# dual-motor-driver.net
KiCad netlist of a schematic drawn in Altium Designer
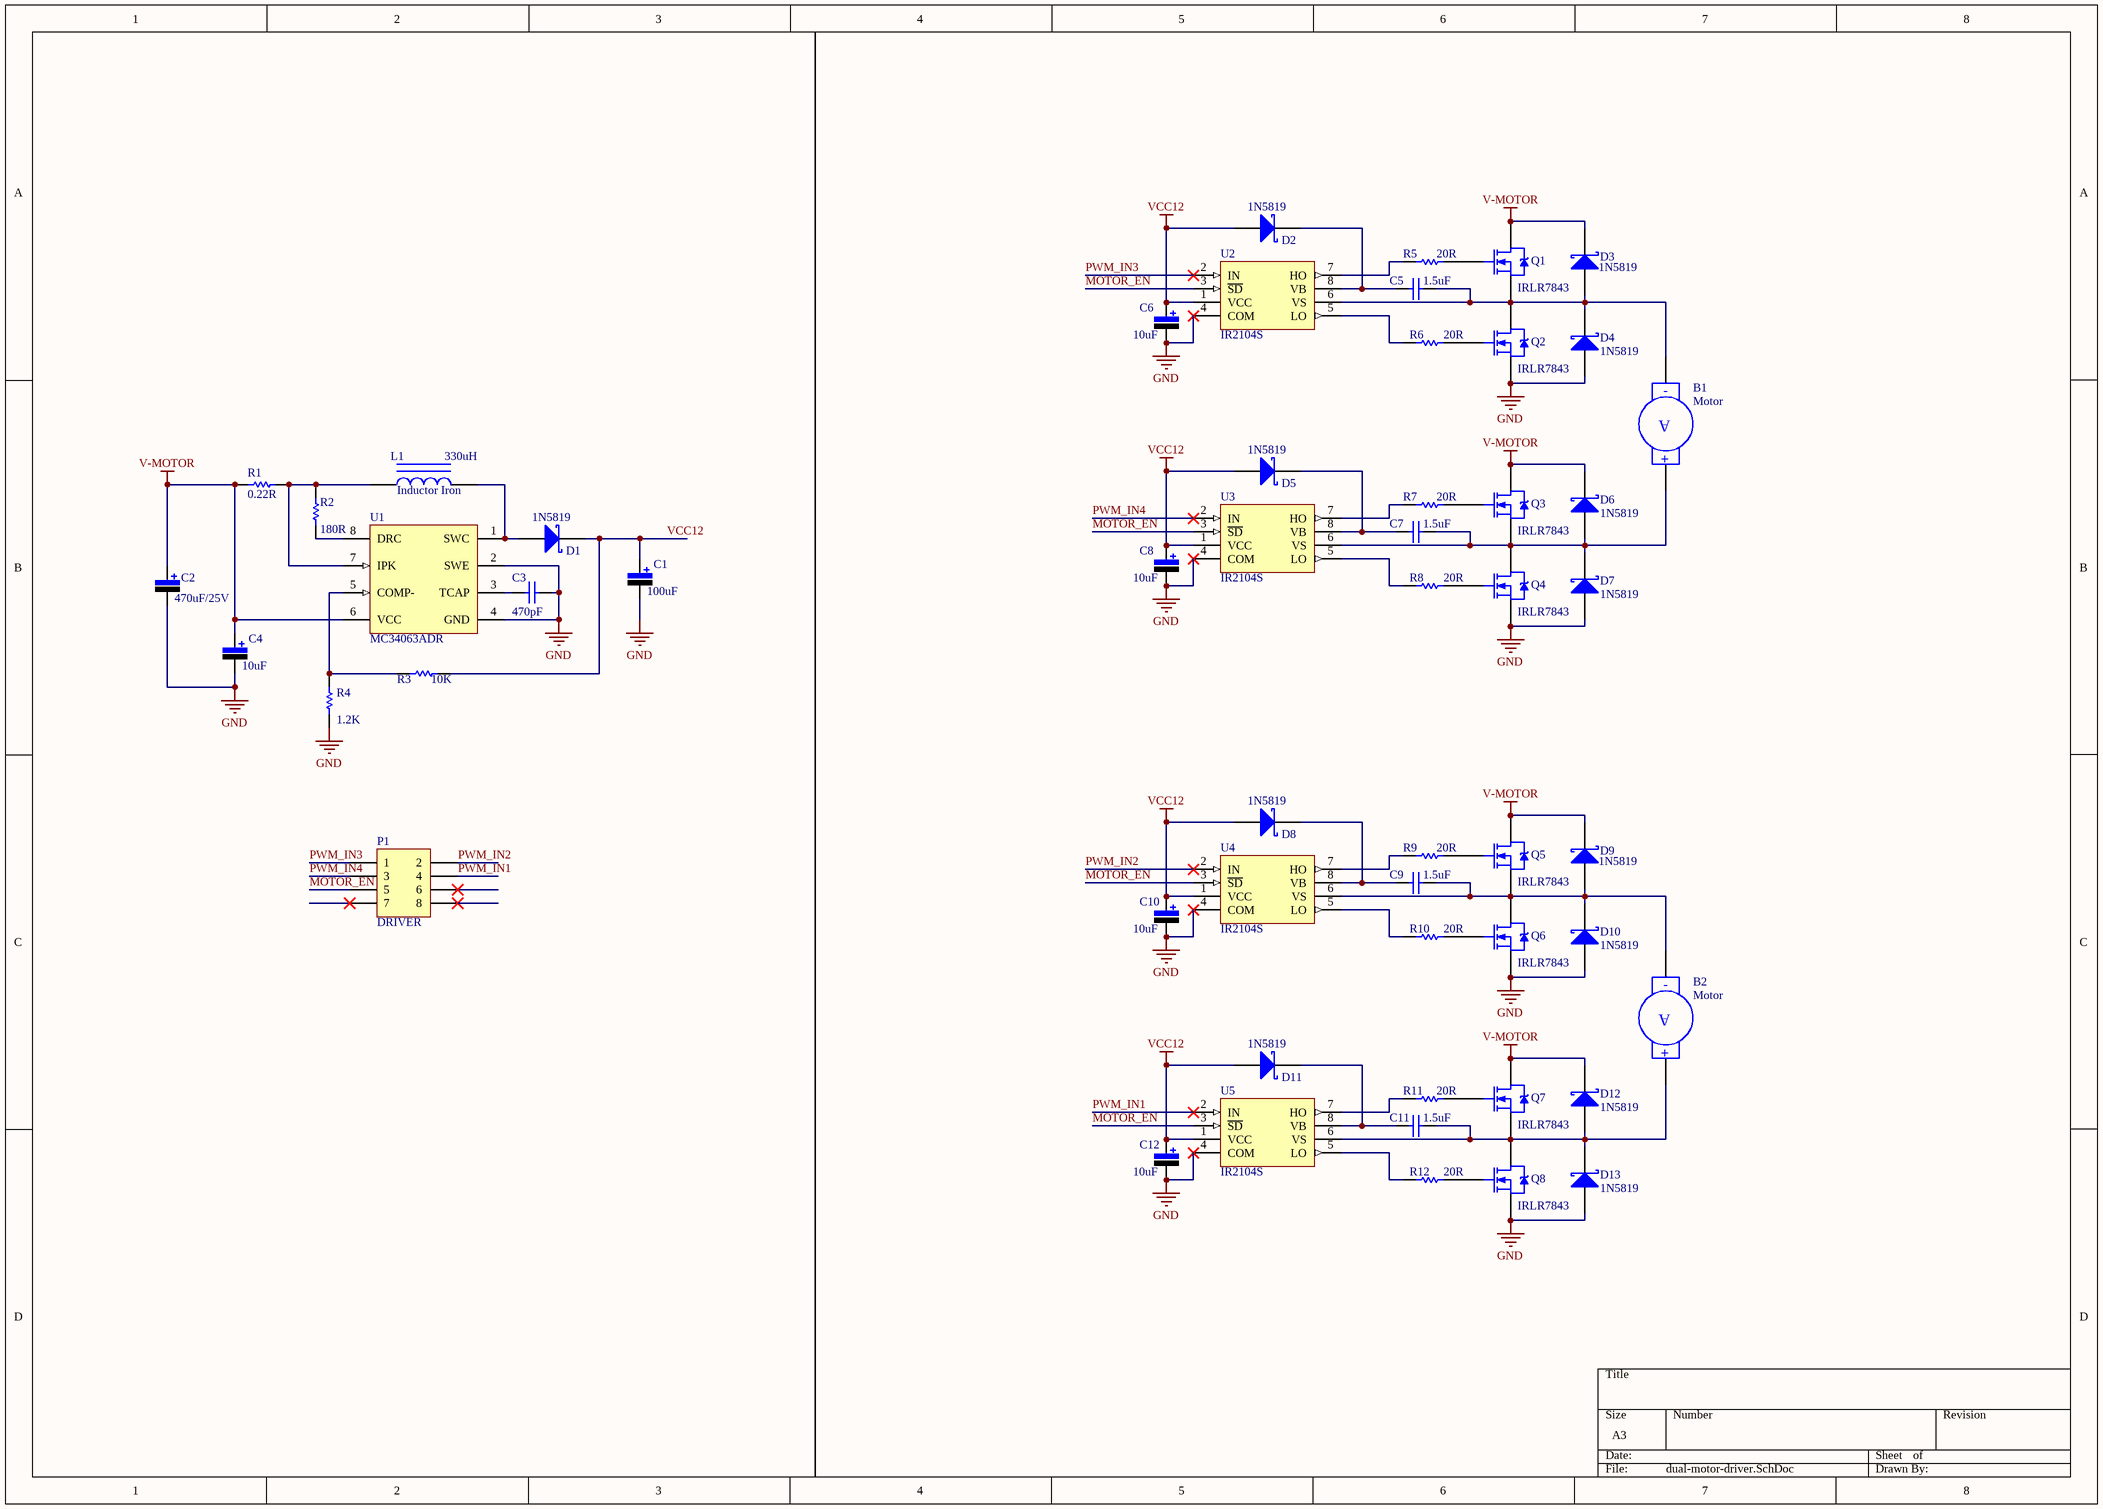
[diagram p0: dual-motor-driver.SchDoc]

(export (version "E")
  (design (tool "Eeschema 10.0.6"))
  (components
    (comp (ref "B1")
      (value "Motor")
      (footprint "Con 2接线端子")
      (description "Servo Motor")
      (fields (field (name "PUBLISHER") "Altium Limited"))
      (libsource (lib "Miscellaneous Devices") (part "Motor Servo"))
    )
    (comp (ref "B2")
      (value "Motor")
      (footprint "Con 2接线端子")
      (description "Servo Motor")
      (fields (field (name "PUBLISHER") "Altium Limited"))
      (libsource (lib "Miscellaneous Devices") (part "Motor Servo"))
    )
    (comp (ref "C1")
      (value "100uF")
      (footprint "LC-CASE-D_7343")
      (description "钽电容")
      (fields (field (name "Comment") "Cap-Pol") (field (name "PUBLISHER") "Altium Limited"))
      (libsource (lib "Fszhang") (part "Cap-Pol-A"))
    )
    (comp (ref "C2")
      (value "470uF/25V")
      (footprint "C-RB-3.5/8")
      (description "贴片铝电解电容")
      (fields (field (name "Comment") "Cap-Pol-ES") (field (name "PUBLISHER") "Altium Limited"))
      (libsource (lib "Fszhang") (part "Cap-Pol-ES"))
    )
    (comp (ref "C3")
      (value "470pF")
      (footprint "LC-0603_C")
      (description "Capacitor")
      (fields (field (name "Comment") "Cap") (field (name "PUBLISHER") "Altium Limited"))
      (libsource (lib "Miscellaneous Devices") (part "Cap"))
    )
    (comp (ref "C4")
      (value "10uF")
      (footprint "LC-CASE-C_6032")
      (description "钽电容")
      (fields (field (name "Comment") "Cap-Pol") (field (name "PUBLISHER") "Altium Limited"))
      (libsource (lib "Fszhang") (part "Cap-Pol-A"))
    )
    (comp (ref "C5")
      (value "1.5uF")
      (footprint "LC-0805_C")
      (description "Capacitor")
      (fields (field (name "Comment") "Cap") (field (name "PUBLISHER") "Altium Limited"))
      (libsource (lib "Miscellaneous Devices") (part "Cap"))
    )
    (comp (ref "C6")
      (value "10uF")
      (footprint "LC-CASE-C_6032")
      (description "钽电容")
      (fields (field (name "Comment") "Cap-Pol") (field (name "PUBLISHER") "Altium Limited"))
      (libsource (lib "Fszhang") (part "Cap-Pol-A"))
    )
    (comp (ref "C7")
      (value "1.5uF")
      (footprint "LC-0805_C")
      (description "Capacitor")
      (fields (field (name "Comment") "Cap") (field (name "PUBLISHER") "Altium Limited"))
      (libsource (lib "Miscellaneous Devices") (part "Cap"))
    )
    (comp (ref "C8")
      (value "10uF")
      (footprint "LC-CASE-C_6032")
      (description "钽电容")
      (fields (field (name "Comment") "Cap-Pol") (field (name "PUBLISHER") "Altium Limited"))
      (libsource (lib "Fszhang") (part "Cap-Pol-A"))
    )
    (comp (ref "C9")
      (value "1.5uF")
      (footprint "LC-0805_C")
      (description "Capacitor")
      (fields (field (name "Comment") "Cap") (field (name "PUBLISHER") "Altium Limited"))
      (libsource (lib "Miscellaneous Devices") (part "Cap"))
    )
    (comp (ref "C10")
      (value "10uF")
      (footprint "LC-CASE-C_6032")
      (description "钽电容")
      (fields (field (name "Comment") "Cap-Pol") (field (name "PUBLISHER") "Altium Limited"))
      (libsource (lib "Fszhang") (part "Cap-Pol-A"))
    )
    (comp (ref "C11")
      (value "1.5uF")
      (footprint "LC-0805_C")
      (description "Capacitor")
      (fields (field (name "Comment") "Cap") (field (name "PUBLISHER") "Altium Limited"))
      (libsource (lib "Miscellaneous Devices") (part "Cap"))
    )
    (comp (ref "C12")
      (value "10uF")
      (footprint "LC-CASE-C_6032")
      (description "钽电容")
      (fields (field (name "Comment") "Cap-Pol") (field (name "PUBLISHER") "Altium Limited"))
      (libsource (lib "Fszhang") (part "Cap-Pol-A"))
    )
    (comp (ref "D1")
      (value "1N5819")
      (footprint "LC-SMA(DO-214AC)_S1")
      (description "Schottky Diode")
      (fields (field (name "PUBLISHER") "Altium Limited"))
      (libsource (lib "Miscellaneous Devices") (part "D Schottky"))
    )
    (comp (ref "D2")
      (value "1N5819")
      (footprint "LC-SMA(DO-214AC)_S1")
      (description "Schottky Diode")
      (fields (field (name "PUBLISHER") "Altium Limited"))
      (libsource (lib "Miscellaneous Devices") (part "D Schottky"))
    )
    (comp (ref "D3")
      (value "1N5819")
      (footprint "LC-SMA(DO-214AC)_S1")
      (description "Schottky Diode")
      (fields (field (name "PUBLISHER") "Altium Limited"))
      (libsource (lib "Miscellaneous Devices") (part "D Schottky"))
    )
    (comp (ref "D4")
      (value "1N5819")
      (footprint "LC-SMA(DO-214AC)_S1")
      (description "Schottky Diode")
      (fields (field (name "PUBLISHER") "Altium Limited"))
      (libsource (lib "Miscellaneous Devices") (part "D Schottky"))
    )
    (comp (ref "D5")
      (value "1N5819")
      (footprint "LC-SMA(DO-214AC)_S1")
      (description "Schottky Diode")
      (fields (field (name "PUBLISHER") "Altium Limited"))
      (libsource (lib "Miscellaneous Devices") (part "D Schottky"))
    )
    (comp (ref "D6")
      (value "1N5819")
      (footprint "LC-SMA(DO-214AC)_S1")
      (description "Schottky Diode")
      (fields (field (name "PUBLISHER") "Altium Limited"))
      (libsource (lib "Miscellaneous Devices") (part "D Schottky"))
    )
    (comp (ref "D7")
      (value "1N5819")
      (footprint "LC-SMA(DO-214AC)_S1")
      (description "Schottky Diode")
      (fields (field (name "PUBLISHER") "Altium Limited"))
      (libsource (lib "Miscellaneous Devices") (part "D Schottky"))
    )
    (comp (ref "D8")
      (value "1N5819")
      (footprint "LC-SMA(DO-214AC)_S1")
      (description "Schottky Diode")
      (fields (field (name "PUBLISHER") "Altium Limited"))
      (libsource (lib "Miscellaneous Devices") (part "D Schottky"))
    )
    (comp (ref "D9")
      (value "1N5819")
      (footprint "LC-SMA(DO-214AC)_S1")
      (description "Schottky Diode")
      (fields (field (name "PUBLISHER") "Altium Limited"))
      (libsource (lib "Miscellaneous Devices") (part "D Schottky"))
    )
    (comp (ref "D10")
      (value "1N5819")
      (footprint "LC-SMA(DO-214AC)_S1")
      (description "Schottky Diode")
      (fields (field (name "PUBLISHER") "Altium Limited"))
      (libsource (lib "Miscellaneous Devices") (part "D Schottky"))
    )
    (comp (ref "D11")
      (value "1N5819")
      (footprint "LC-SMA(DO-214AC)_S1")
      (description "Schottky Diode")
      (fields (field (name "PUBLISHER") "Altium Limited"))
      (libsource (lib "Miscellaneous Devices") (part "D Schottky"))
    )
    (comp (ref "D12")
      (value "1N5819")
      (footprint "LC-SMA(DO-214AC)_S1")
      (description "Schottky Diode")
      (fields (field (name "PUBLISHER") "Altium Limited"))
      (libsource (lib "Miscellaneous Devices") (part "D Schottky"))
    )
    (comp (ref "D13")
      (value "1N5819")
      (footprint "LC-SMA(DO-214AC)_S1")
      (description "Schottky Diode")
      (fields (field (name "PUBLISHER") "Altium Limited"))
      (libsource (lib "Miscellaneous Devices") (part "D Schottky"))
    )
    (comp (ref "L1")
      (value "Inductor Iron")
      (footprint "L-SMD-12")
      (description "Magnetic-Core Inductor")
      (fields (field (name "ALTIUM_VALUE") "330uH") (field (name "PUBLISHER") "Altium Limited"))
      (libsource (lib "Miscellaneous Devices") (part "Inductor Iron"))
    )
    (comp (ref "P1")
      (value "DRIVER")
      (footprint "MHDR2X4")
      (description "电机驱动接口")
      (fields (field (name "PUBLISHER") "Altium Limited"))
      (libsource (lib "Miscellaneous Connectors") (part "Header 4X2"))
    )
    (comp (ref "Q1")
      (value "IRLR7843")
      (footprint "TO-252AA_M")
      (description "HEXFET Power MOSFET")
      (fields (field (name "PUBLISHER") "Altium Limited"))
      (libsource (lib "IR Discrete MOSFET - Power") (part "IRLR8503"))
    )
    (comp (ref "Q2")
      (value "IRLR7843")
      (footprint "TO-252AA_M")
      (description "HEXFET Power MOSFET")
      (fields (field (name "PUBLISHER") "Altium Limited"))
      (libsource (lib "IR Discrete MOSFET - Power") (part "IRLR8503"))
    )
    (comp (ref "Q3")
      (value "IRLR7843")
      (footprint "TO-252AA_M")
      (description "HEXFET Power MOSFET")
      (fields (field (name "PUBLISHER") "Altium Limited"))
      (libsource (lib "IR Discrete MOSFET - Power") (part "IRLR8503"))
    )
    (comp (ref "Q4")
      (value "IRLR7843")
      (footprint "TO-252AA_M")
      (description "HEXFET Power MOSFET")
      (fields (field (name "PUBLISHER") "Altium Limited"))
      (libsource (lib "IR Discrete MOSFET - Power") (part "IRLR8503"))
    )
    (comp (ref "Q5")
      (value "IRLR7843")
      (footprint "TO-252AA_M")
      (description "HEXFET Power MOSFET")
      (fields (field (name "PUBLISHER") "Altium Limited"))
      (libsource (lib "IR Discrete MOSFET - Power") (part "IRLR8503"))
    )
    (comp (ref "Q6")
      (value "IRLR7843")
      (footprint "TO-252AA_M")
      (description "HEXFET Power MOSFET")
      (fields (field (name "PUBLISHER") "Altium Limited"))
      (libsource (lib "IR Discrete MOSFET - Power") (part "IRLR8503"))
    )
    (comp (ref "Q7")
      (value "IRLR7843")
      (footprint "TO-252AA_M")
      (description "HEXFET Power MOSFET")
      (fields (field (name "PUBLISHER") "Altium Limited"))
      (libsource (lib "IR Discrete MOSFET - Power") (part "IRLR8503"))
    )
    (comp (ref "Q8")
      (value "IRLR7843")
      (footprint "TO-252AA_M")
      (description "HEXFET Power MOSFET")
      (fields (field (name "PUBLISHER") "Altium Limited"))
      (libsource (lib "IR Discrete MOSFET - Power") (part "IRLR8503"))
    )
    (comp (ref "R1")
      (value "0.22R")
      (footprint "LC-0603_R")
      (description "Resistor")
      (fields (field (name "Comment") "Res1") (field (name "PUBLISHER") "Altium Limited"))
      (libsource (lib "Miscellaneous Devices") (part "Res1"))
    )
    (comp (ref "R2")
      (value "180R")
      (footprint "LC-0603_R")
      (description "Resistor")
      (fields (field (name "Comment") "Res1") (field (name "PUBLISHER") "Altium Limited"))
      (libsource (lib "Miscellaneous Devices") (part "Res1"))
    )
    (comp (ref "R3")
      (value "10K")
      (footprint "LC-0603_R")
      (description "Resistor")
      (fields (field (name "Comment") "Res1") (field (name "PUBLISHER") "Altium Limited"))
      (libsource (lib "Miscellaneous Devices") (part "Res1"))
    )
    (comp (ref "R4")
      (value "1.2K")
      (footprint "LC-0603_R")
      (description "Resistor")
      (fields (field (name "Comment") "Res1") (field (name "PUBLISHER") "Altium Limited"))
      (libsource (lib "Miscellaneous Devices") (part "Res1"))
    )
    (comp (ref "R5")
      (value "20R")
      (footprint "LC-0603_R")
      (description "Resistor")
      (fields (field (name "Comment") "Res1") (field (name "PUBLISHER") "Altium Limited"))
      (libsource (lib "Miscellaneous Devices") (part "Res1"))
    )
    (comp (ref "R6")
      (value "20R")
      (footprint "LC-0603_R")
      (description "Resistor")
      (fields (field (name "Comment") "Res1") (field (name "PUBLISHER") "Altium Limited"))
      (libsource (lib "Miscellaneous Devices") (part "Res1"))
    )
    (comp (ref "R7")
      (value "20R")
      (footprint "LC-0603_R")
      (description "Resistor")
      (fields (field (name "Comment") "Res1") (field (name "PUBLISHER") "Altium Limited"))
      (libsource (lib "Miscellaneous Devices") (part "Res1"))
    )
    (comp (ref "R8")
      (value "20R")
      (footprint "LC-0603_R")
      (description "Resistor")
      (fields (field (name "Comment") "Res1") (field (name "PUBLISHER") "Altium Limited"))
      (libsource (lib "Miscellaneous Devices") (part "Res1"))
    )
    (comp (ref "R9")
      (value "20R")
      (footprint "LC-0603_R")
      (description "Resistor")
      (fields (field (name "Comment") "Res1") (field (name "PUBLISHER") "Altium Limited"))
      (libsource (lib "Miscellaneous Devices") (part "Res1"))
    )
    (comp (ref "R10")
      (value "20R")
      (footprint "LC-0603_R")
      (description "Resistor")
      (fields (field (name "Comment") "Res1") (field (name "PUBLISHER") "Altium Limited"))
      (libsource (lib "Miscellaneous Devices") (part "Res1"))
    )
    (comp (ref "R11")
      (value "20R")
      (footprint "LC-0603_R")
      (description "Resistor")
      (fields (field (name "Comment") "Res1") (field (name "PUBLISHER") "Altium Limited"))
      (libsource (lib "Miscellaneous Devices") (part "Res1"))
    )
    (comp (ref "R12")
      (value "20R")
      (footprint "LC-0603_R")
      (description "Resistor")
      (fields (field (name "Comment") "Res1") (field (name "PUBLISHER") "Altium Limited"))
      (libsource (lib "Miscellaneous Devices") (part "Res1"))
    )
    (comp (ref "U1")
      (value "MC34063ADR")
      (footprint "LC-SOIC-8_150mil")
      (fields (field (name "MANUFACTURER") "Texas Instruments"))
      (libsource (lib "TI Power Management Step-Down Regulator") (part "MC34063ADR"))
    )
    (comp (ref "U2")
      (value "IR2104S")
      (footprint "SO-8_N")
      (description "High and Low Side Driver")
      (fields (field (name "PUBLISHER") "Altium Limited"))
      (libsource (lib "IR Interface Bridge Driver") (part "IR2104S"))
    )
    (comp (ref "U3")
      (value "IR2104S")
      (footprint "SO-8_N")
      (description "High and Low Side Driver")
      (fields (field (name "PUBLISHER") "Altium Limited"))
      (libsource (lib "IR Interface Bridge Driver") (part "IR2104S"))
    )
    (comp (ref "U4")
      (value "IR2104S")
      (footprint "SO-8_N")
      (description "High and Low Side Driver")
      (fields (field (name "PUBLISHER") "Altium Limited"))
      (libsource (lib "IR Interface Bridge Driver") (part "IR2104S"))
    )
    (comp (ref "U5")
      (value "IR2104S")
      (footprint "SO-8_N")
      (description "High and Low Side Driver")
      (fields (field (name "PUBLISHER") "Altium Limited"))
      (libsource (lib "IR Interface Bridge Driver") (part "IR2104S"))
    )
  )
  (nets
    (net (code "1") (name "/MOTOR_EN") (class "Default")
      (node (ref "P1") (pin "5") (pinfunction "5_5") (pintype "passive"))
      (node (ref "U2") (pin "3") (pinfunction "~{SD}_3") (pintype "input"))
      (node (ref "U3") (pin "3") (pinfunction "~{SD}_3") (pintype "input"))
      (node (ref "U4") (pin "3") (pinfunction "~{SD}_3") (pintype "input"))
      (node (ref "U5") (pin "3") (pinfunction "~{SD}_3") (pintype "input"))
    )
    (net (code "2") (name "/PWM_IN1") (class "Default")
      (node (ref "P1") (pin "4") (pinfunction "4_4") (pintype "passive"))
      (node (ref "U5") (pin "2") (pinfunction "IN_2") (pintype "input"))
    )
    (net (code "3") (name "/PWM_IN2") (class "Default")
      (node (ref "P1") (pin "2") (pinfunction "2_2") (pintype "passive"))
      (node (ref "U4") (pin "2") (pinfunction "IN_2") (pintype "input"))
    )
    (net (code "4") (name "/PWM_IN3") (class "Default")
      (node (ref "P1") (pin "1") (pinfunction "1_1") (pintype "passive"))
      (node (ref "U2") (pin "2") (pinfunction "IN_2") (pintype "input"))
    )
    (net (code "5") (name "/PWM_IN4") (class "Default")
      (node (ref "P1") (pin "3") (pinfunction "3_3") (pintype "passive"))
      (node (ref "U3") (pin "2") (pinfunction "IN_2") (pintype "input"))
    )
    (net (code "6") (name "GND") (class "Default")
      (node (ref "C1") (pin "2") (pinfunction "2_2") (pintype "passive"))
      (node (ref "C10") (pin "2") (pinfunction "2_2") (pintype "passive"))
      (node (ref "C12") (pin "2") (pinfunction "2_2") (pintype "passive"))
      (node (ref "C2") (pin "2") (pinfunction "2_2") (pintype "passive"))
      (node (ref "C3") (pin "1") (pinfunction "1_1") (pintype "passive"))
      (node (ref "C4") (pin "2") (pinfunction "2_2") (pintype "passive"))
      (node (ref "C6") (pin "2") (pinfunction "2_2") (pintype "passive"))
      (node (ref "C8") (pin "2") (pinfunction "2_2") (pintype "passive"))
      (node (ref "D10") (pin "1") (pinfunction "A_1") (pintype "passive"))
      (node (ref "D13") (pin "1") (pinfunction "A_1") (pintype "passive"))
      (node (ref "D4") (pin "1") (pinfunction "A_1") (pintype "passive"))
      (node (ref "D7") (pin "1") (pinfunction "A_1") (pintype "passive"))
      (node (ref "Q2") (pin "3") (pinfunction "S_3") (pintype "passive"))
      (node (ref "Q4") (pin "3") (pinfunction "S_3") (pintype "passive"))
      (node (ref "Q6") (pin "3") (pinfunction "S_3") (pintype "passive"))
      (node (ref "Q8") (pin "3") (pinfunction "S_3") (pintype "passive"))
      (node (ref "R4") (pin "1") (pinfunction "1_1") (pintype "passive"))
      (node (ref "U1") (pin "2") (pinfunction "SWE_2") (pintype "open_emitter"))
      (node (ref "U1") (pin "4") (pinfunction "GND_4") (pintype "power_in"))
      (node (ref "U2") (pin "4") (pinfunction "COM_4") (pintype "power_in"))
      (node (ref "U3") (pin "4") (pinfunction "COM_4") (pintype "power_in"))
      (node (ref "U4") (pin "4") (pinfunction "COM_4") (pintype "power_in"))
      (node (ref "U5") (pin "4") (pinfunction "COM_4") (pintype "power_in"))
    )
    (net (code "7") (name "Net-(B1-+)") (class "Default")
      (node (ref "B1") (pin "1") (pinfunction "+_1") (pintype "passive"))
      (node (ref "C5") (pin "2") (pinfunction "2_2") (pintype "passive"))
      (node (ref "D3") (pin "1") (pinfunction "A_1") (pintype "passive"))
      (node (ref "D4") (pin "2") (pinfunction "K_2") (pintype "passive"))
      (node (ref "Q1") (pin "3") (pinfunction "S_3") (pintype "passive"))
      (node (ref "Q2") (pin "4") (pinfunction "D_4") (pintype "passive"))
      (node (ref "U2") (pin "6") (pinfunction "VS_6") (pintype "power_in"))
    )
    (net (code "8") (name "Net-(B1--)") (class "Default")
      (node (ref "B1") (pin "2") (pinfunction "-_2") (pintype "passive"))
      (node (ref "C7") (pin "2") (pinfunction "2_2") (pintype "passive"))
      (node (ref "D6") (pin "1") (pinfunction "A_1") (pintype "passive"))
      (node (ref "D7") (pin "2") (pinfunction "K_2") (pintype "passive"))
      (node (ref "Q3") (pin "3") (pinfunction "S_3") (pintype "passive"))
      (node (ref "Q4") (pin "4") (pinfunction "D_4") (pintype "passive"))
      (node (ref "U3") (pin "6") (pinfunction "VS_6") (pintype "power_in"))
    )
    (net (code "9") (name "Net-(B2-+)") (class "Default")
      (node (ref "B2") (pin "1") (pinfunction "+_1") (pintype "passive"))
      (node (ref "C9") (pin "2") (pinfunction "2_2") (pintype "passive"))
      (node (ref "D10") (pin "2") (pinfunction "K_2") (pintype "passive"))
      (node (ref "D9") (pin "1") (pinfunction "A_1") (pintype "passive"))
      (node (ref "Q5") (pin "3") (pinfunction "S_3") (pintype "passive"))
      (node (ref "Q6") (pin "4") (pinfunction "D_4") (pintype "passive"))
      (node (ref "U4") (pin "6") (pinfunction "VS_6") (pintype "power_in"))
    )
    (net (code "10") (name "Net-(B2--)") (class "Default")
      (node (ref "B2") (pin "2") (pinfunction "-_2") (pintype "passive"))
      (node (ref "C11") (pin "2") (pinfunction "2_2") (pintype "passive"))
      (node (ref "D12") (pin "1") (pinfunction "A_1") (pintype "passive"))
      (node (ref "D13") (pin "2") (pinfunction "K_2") (pintype "passive"))
      (node (ref "Q7") (pin "3") (pinfunction "S_3") (pintype "passive"))
      (node (ref "Q8") (pin "4") (pinfunction "D_4") (pintype "passive"))
      (node (ref "U5") (pin "6") (pinfunction "VS_6") (pintype "power_in"))
    )
    (net (code "11") (name "Net-(D1-A)") (class "Default")
      (node (ref "D1") (pin "1") (pinfunction "A_1") (pintype "passive"))
      (node (ref "L1") (pin "2") (pinfunction "2_2") (pintype "passive"))
      (node (ref "U1") (pin "1") (pinfunction "SWC_1") (pintype "open_collector"))
    )
    (net (code "12") (name "Net-(D2-K)") (class "Default")
      (node (ref "C5") (pin "1") (pinfunction "1_1") (pintype "passive"))
      (node (ref "D2") (pin "2") (pinfunction "K_2") (pintype "passive"))
      (node (ref "U2") (pin "8") (pinfunction "VB_8") (pintype "power_in"))
    )
    (net (code "13") (name "Net-(D5-K)") (class "Default")
      (node (ref "C7") (pin "1") (pinfunction "1_1") (pintype "passive"))
      (node (ref "D5") (pin "2") (pinfunction "K_2") (pintype "passive"))
      (node (ref "U3") (pin "8") (pinfunction "VB_8") (pintype "power_in"))
    )
    (net (code "14") (name "Net-(D8-K)") (class "Default")
      (node (ref "C9") (pin "1") (pinfunction "1_1") (pintype "passive"))
      (node (ref "D8") (pin "2") (pinfunction "K_2") (pintype "passive"))
      (node (ref "U4") (pin "8") (pinfunction "VB_8") (pintype "power_in"))
    )
    (net (code "15") (name "Net-(D11-K)") (class "Default")
      (node (ref "C11") (pin "1") (pinfunction "1_1") (pintype "passive"))
      (node (ref "D11") (pin "2") (pinfunction "K_2") (pintype "passive"))
      (node (ref "U5") (pin "8") (pinfunction "VB_8") (pintype "power_in"))
    )
    (net (code "16") (name "Net-(Q1-G)") (class "Default")
      (node (ref "Q1") (pin "1") (pinfunction "G_1") (pintype "passive"))
      (node (ref "R5") (pin "1") (pinfunction "1_1") (pintype "passive"))
    )
    (net (code "17") (name "Net-(Q2-G)") (class "Default")
      (node (ref "Q2") (pin "1") (pinfunction "G_1") (pintype "passive"))
      (node (ref "R6") (pin "1") (pinfunction "1_1") (pintype "passive"))
    )
    (net (code "18") (name "Net-(Q3-G)") (class "Default")
      (node (ref "Q3") (pin "1") (pinfunction "G_1") (pintype "passive"))
      (node (ref "R7") (pin "1") (pinfunction "1_1") (pintype "passive"))
    )
    (net (code "19") (name "Net-(Q4-G)") (class "Default")
      (node (ref "Q4") (pin "1") (pinfunction "G_1") (pintype "passive"))
      (node (ref "R8") (pin "1") (pinfunction "1_1") (pintype "passive"))
    )
    (net (code "20") (name "Net-(Q5-G)") (class "Default")
      (node (ref "Q5") (pin "1") (pinfunction "G_1") (pintype "passive"))
      (node (ref "R9") (pin "1") (pinfunction "1_1") (pintype "passive"))
    )
    (net (code "21") (name "Net-(Q6-G)") (class "Default")
      (node (ref "Q6") (pin "1") (pinfunction "G_1") (pintype "passive"))
      (node (ref "R10") (pin "1") (pinfunction "1_1") (pintype "passive"))
    )
    (net (code "22") (name "Net-(Q7-G)") (class "Default")
      (node (ref "Q7") (pin "1") (pinfunction "G_1") (pintype "passive"))
      (node (ref "R11") (pin "1") (pinfunction "1_1") (pintype "passive"))
    )
    (net (code "23") (name "Net-(Q8-G)") (class "Default")
      (node (ref "Q8") (pin "1") (pinfunction "G_1") (pintype "passive"))
      (node (ref "R12") (pin "1") (pinfunction "1_1") (pintype "passive"))
    )
    (net (code "24") (name "Net-(U1-COMP-)") (class "Default")
      (node (ref "R3") (pin "2") (pinfunction "2_2") (pintype "passive"))
      (node (ref "R4") (pin "2") (pinfunction "2_2") (pintype "passive"))
      (node (ref "U1") (pin "5") (pinfunction "COMP-_5") (pintype "input"))
    )
    (net (code "25") (name "Net-(U1-DRC)") (class "Default")
      (node (ref "R2") (pin "1") (pinfunction "1_1") (pintype "passive"))
      (node (ref "U1") (pin "8") (pinfunction "DRC_8") (pintype "open_collector"))
    )
    (net (code "26") (name "Net-(U1-IPK)") (class "Default")
      (node (ref "L1") (pin "1") (pinfunction "1_1") (pintype "passive"))
      (node (ref "R1") (pin "1") (pinfunction "1_1") (pintype "passive"))
      (node (ref "R2") (pin "2") (pinfunction "2_2") (pintype "passive"))
      (node (ref "U1") (pin "7") (pinfunction "IPK_7") (pintype "input"))
    )
    (net (code "27") (name "Net-(U1-TCAP)") (class "Default")
      (node (ref "C3") (pin "2") (pinfunction "2_2") (pintype "passive"))
      (node (ref "U1") (pin "3") (pinfunction "TCAP_3") (pintype "passive"))
    )
    (net (code "28") (name "Net-(U2-HO)") (class "Default")
      (node (ref "R5") (pin "2") (pinfunction "2_2") (pintype "passive"))
      (node (ref "U2") (pin "7") (pinfunction "HO_7") (pintype "output"))
    )
    (net (code "29") (name "Net-(U2-LO)") (class "Default")
      (node (ref "R6") (pin "2") (pinfunction "2_2") (pintype "passive"))
      (node (ref "U2") (pin "5") (pinfunction "LO_5") (pintype "output"))
    )
    (net (code "30") (name "Net-(U3-HO)") (class "Default")
      (node (ref "R7") (pin "2") (pinfunction "2_2") (pintype "passive"))
      (node (ref "U3") (pin "7") (pinfunction "HO_7") (pintype "output"))
    )
    (net (code "31") (name "Net-(U3-LO)") (class "Default")
      (node (ref "R8") (pin "2") (pinfunction "2_2") (pintype "passive"))
      (node (ref "U3") (pin "5") (pinfunction "LO_5") (pintype "output"))
    )
    (net (code "32") (name "Net-(U4-HO)") (class "Default")
      (node (ref "R9") (pin "2") (pinfunction "2_2") (pintype "passive"))
      (node (ref "U4") (pin "7") (pinfunction "HO_7") (pintype "output"))
    )
    (net (code "33") (name "Net-(U4-LO)") (class "Default")
      (node (ref "R10") (pin "2") (pinfunction "2_2") (pintype "passive"))
      (node (ref "U4") (pin "5") (pinfunction "LO_5") (pintype "output"))
    )
    (net (code "34") (name "Net-(U5-HO)") (class "Default")
      (node (ref "R11") (pin "2") (pinfunction "2_2") (pintype "passive"))
      (node (ref "U5") (pin "7") (pinfunction "HO_7") (pintype "output"))
    )
    (net (code "35") (name "Net-(U5-LO)") (class "Default")
      (node (ref "R12") (pin "2") (pinfunction "2_2") (pintype "passive"))
      (node (ref "U5") (pin "5") (pinfunction "LO_5") (pintype "output"))
    )
    (net (code "36") (name "V-MOTOR") (class "Default")
      (node (ref "C2") (pin "1") (pinfunction "1_1") (pintype "passive"))
      (node (ref "C4") (pin "1") (pinfunction "1_1") (pintype "passive"))
      (node (ref "D12") (pin "2") (pinfunction "K_2") (pintype "passive"))
      (node (ref "D3") (pin "2") (pinfunction "K_2") (pintype "passive"))
      (node (ref "D6") (pin "2") (pinfunction "K_2") (pintype "passive"))
      (node (ref "D9") (pin "2") (pinfunction "K_2") (pintype "passive"))
      (node (ref "Q1") (pin "4") (pinfunction "D_4") (pintype "passive"))
      (node (ref "Q3") (pin "4") (pinfunction "D_4") (pintype "passive"))
      (node (ref "Q5") (pin "4") (pinfunction "D_4") (pintype "passive"))
      (node (ref "Q7") (pin "4") (pinfunction "D_4") (pintype "passive"))
      (node (ref "R1") (pin "2") (pinfunction "2_2") (pintype "passive"))
      (node (ref "U1") (pin "6") (pinfunction "VCC_6") (pintype "power_in"))
    )
    (net (code "37") (name "VCC12") (class "Default")
      (node (ref "C1") (pin "1") (pinfunction "1_1") (pintype "passive"))
      (node (ref "C10") (pin "1") (pinfunction "1_1") (pintype "passive"))
      (node (ref "C12") (pin "1") (pinfunction "1_1") (pintype "passive"))
      (node (ref "C6") (pin "1") (pinfunction "1_1") (pintype "passive"))
      (node (ref "C8") (pin "1") (pinfunction "1_1") (pintype "passive"))
      (node (ref "D1") (pin "2") (pinfunction "K_2") (pintype "passive"))
      (node (ref "D11") (pin "1") (pinfunction "A_1") (pintype "passive"))
      (node (ref "D2") (pin "1") (pinfunction "A_1") (pintype "passive"))
      (node (ref "D5") (pin "1") (pinfunction "A_1") (pintype "passive"))
      (node (ref "D8") (pin "1") (pinfunction "A_1") (pintype "passive"))
      (node (ref "R3") (pin "1") (pinfunction "1_1") (pintype "passive"))
      (node (ref "U2") (pin "1") (pinfunction "VCC_1") (pintype "power_in"))
      (node (ref "U3") (pin "1") (pinfunction "VCC_1") (pintype "power_in"))
      (node (ref "U4") (pin "1") (pinfunction "VCC_1") (pintype "power_in"))
      (node (ref "U5") (pin "1") (pinfunction "VCC_1") (pintype "power_in"))
    )
    (net (code "38") (name "unconnected-(P1-Pad6)") (class "Default")
      (node (ref "P1") (pin "6") (pinfunction "6_6") (pintype "passive+no_connect"))
    )
    (net (code "39") (name "unconnected-(P1-Pad7)") (class "Default")
      (node (ref "P1") (pin "7") (pinfunction "7_7") (pintype "passive+no_connect"))
    )
    (net (code "40") (name "unconnected-(P1-Pad8)") (class "Default")
      (node (ref "P1") (pin "8") (pinfunction "8_8") (pintype "passive+no_connect"))
    )
  )
)
